# r6.net
KiCad netlist of a schematic drawn in EasyEDA
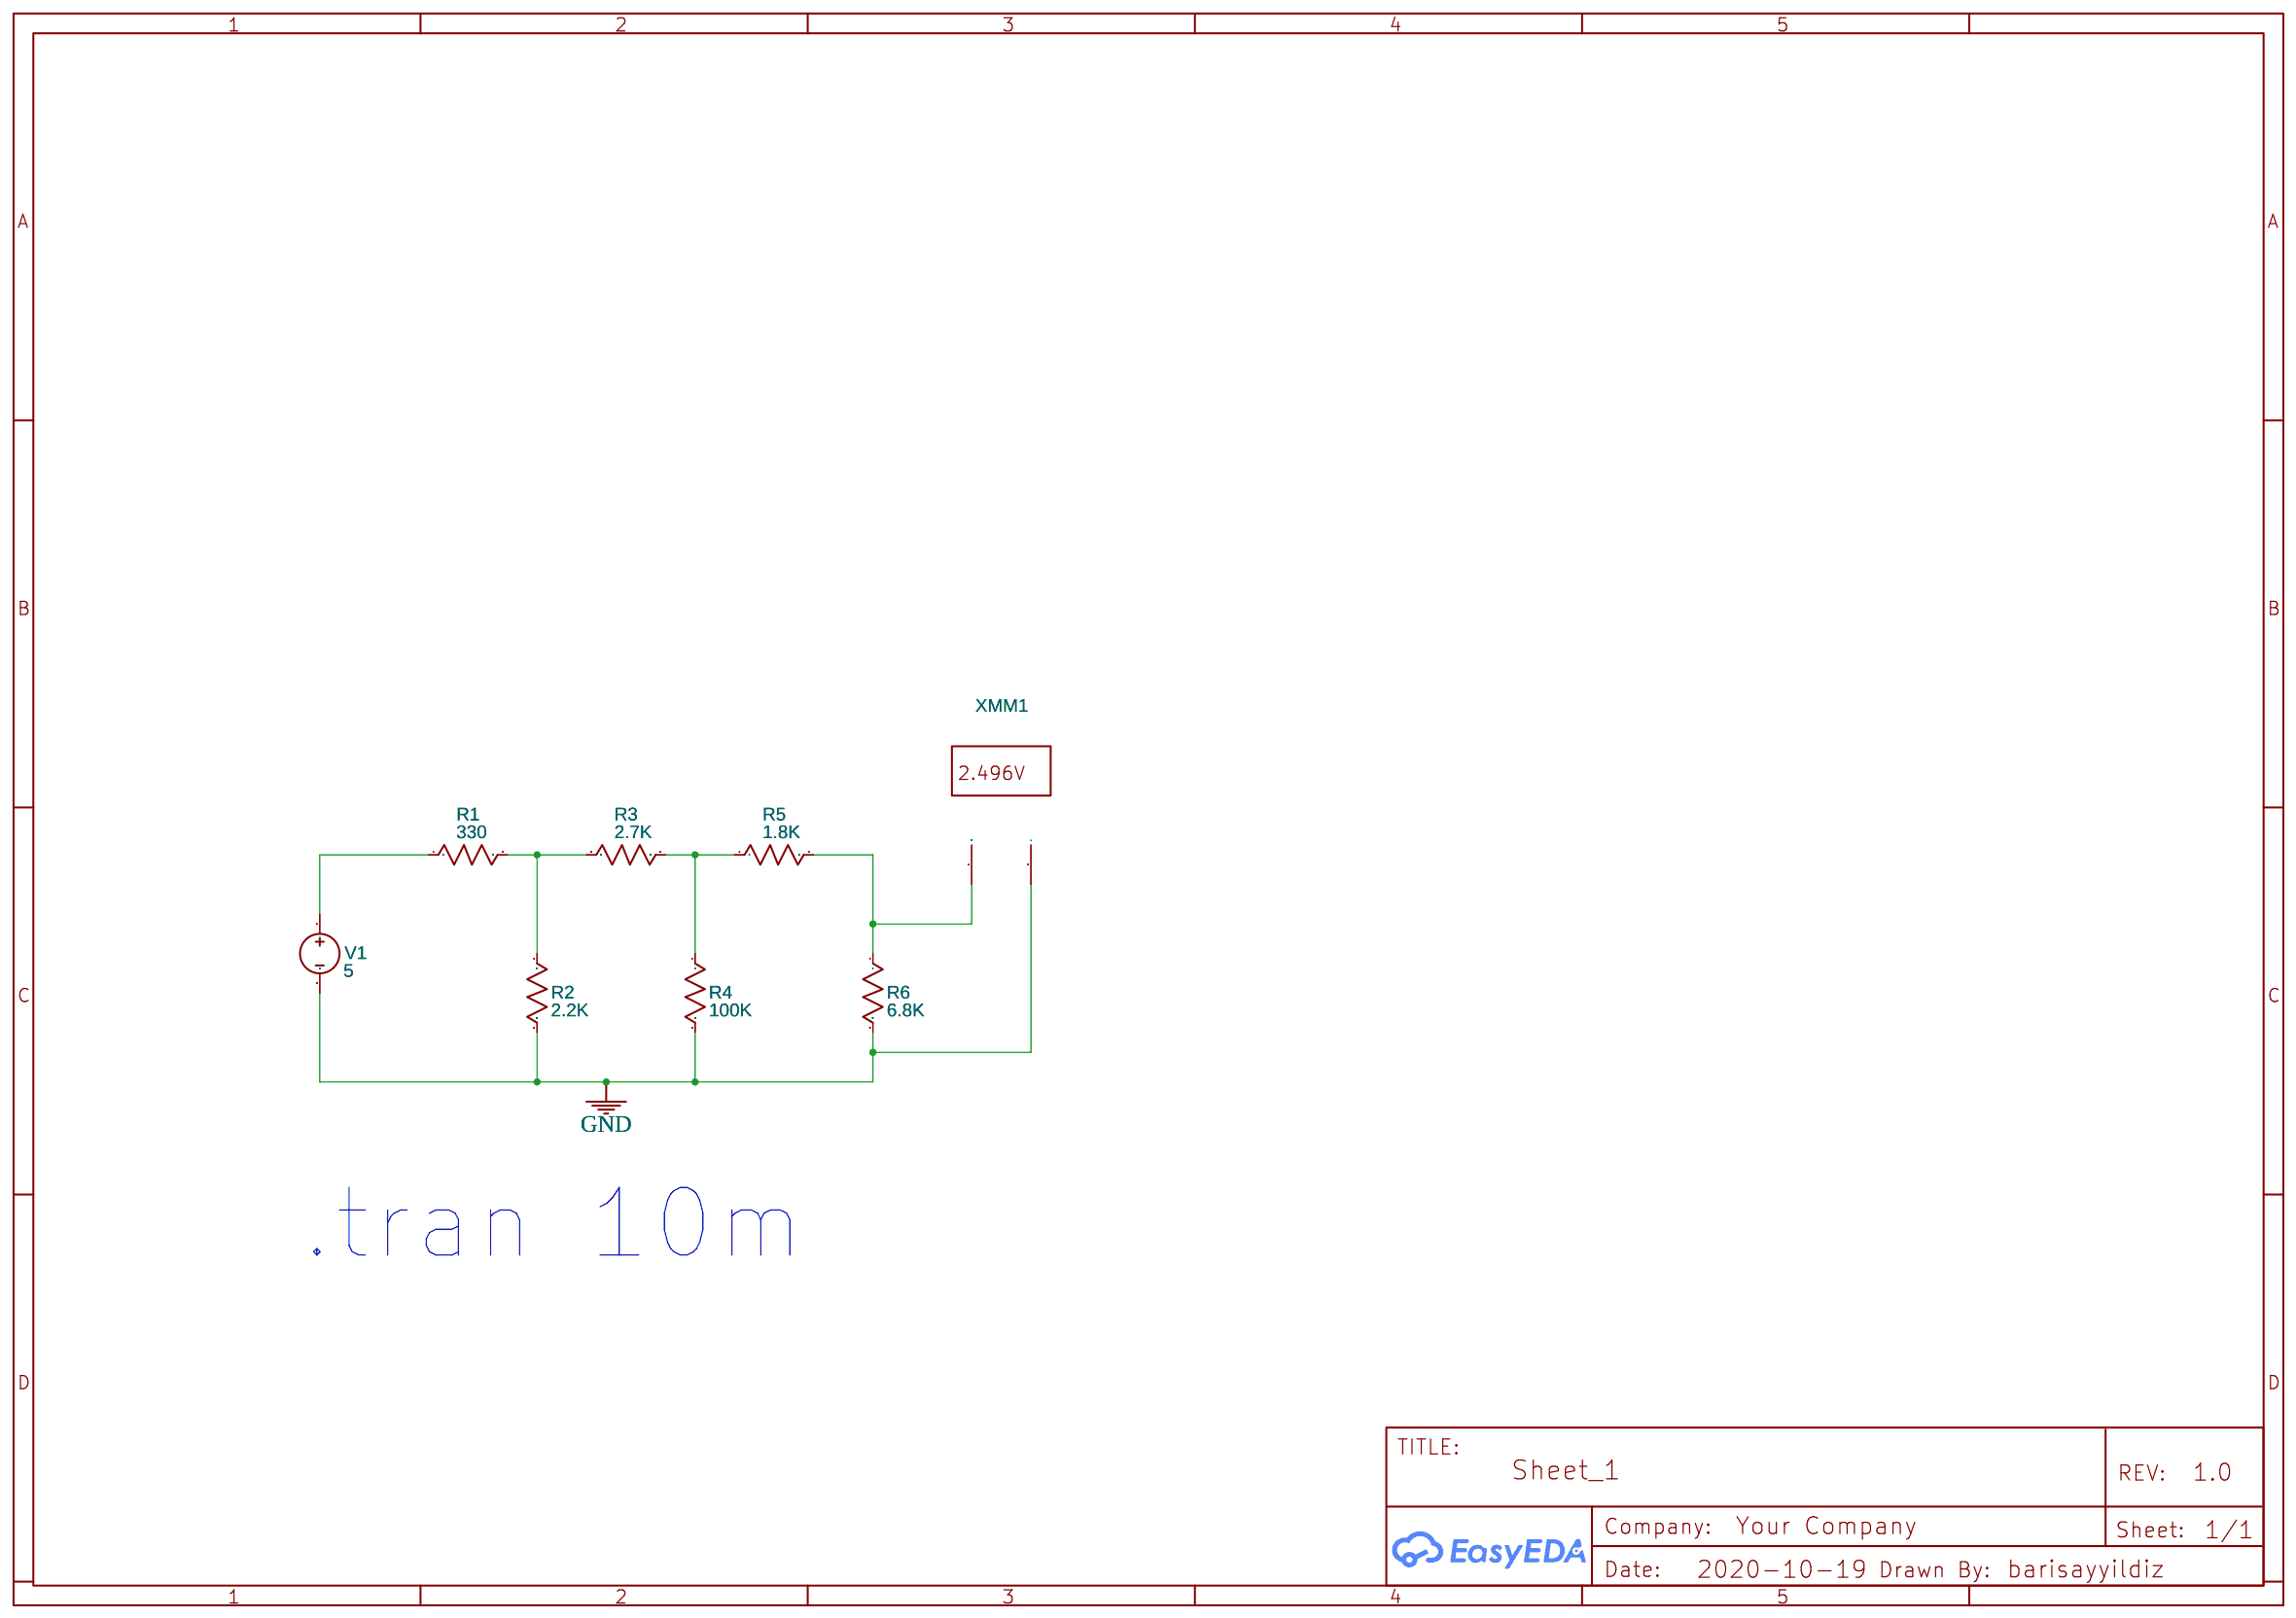
[diagram p0: schematic sheet]

(export (version "E")
  (design (tool "Eeschema 10.0.6"))
  (components
    (comp (ref "R1") (value "330") (libsource (lib "") (part "Resistor_US")))
    (comp (ref "R2") (value "2.2K") (libsource (lib "") (part "Resistor_US_1")))
    (comp (ref "R3") (value "2.7K") (libsource (lib "") (part "Resistor_US")))
    (comp (ref "R4") (value "100K") (libsource (lib "") (part "Resistor_US_1")))
    (comp (ref "R5") (value "1.8K") (libsource (lib "") (part "Resistor_US")))
    (comp (ref "R6") (value "6.8K") (libsource (lib "") (part "Resistor_US_1")))
    (comp (ref "V1") (value "5") (libsource (lib "") (part "VDC")))
    (comp (ref "XMM1") (value "Multimeter") (libsource (lib "") (part "MULTIMETER")))
  )
  (nets
    (net (code "1") (name "GND") (class "Default")
      (node (ref "R2") (pin "2") (pinfunction "2_2") (pintype "unspecified"))
      (node (ref "R4") (pin "2") (pinfunction "2_2") (pintype "unspecified"))
      (node (ref "R6") (pin "2") (pinfunction "2_2") (pintype "unspecified"))
      (node (ref "V1") (pin "2") (pinfunction "2_2") (pintype "unspecified"))
      (node (ref "XMM1") (pin "2") (pinfunction "I_2") (pintype "unspecified"))
    )
    (net (code "2") (name "Net-(R1-Pad1)") (class "Default")
      (node (ref "R1") (pin "1") (pinfunction "1_1") (pintype "unspecified"))
      (node (ref "V1") (pin "1") (pinfunction "1_1") (pintype "unspecified"))
    )
    (net (code "3") (name "Net-(R1-Pad2)") (class "Default")
      (node (ref "R1") (pin "2") (pinfunction "2_2") (pintype "unspecified"))
      (node (ref "R2") (pin "1") (pinfunction "1_1") (pintype "unspecified"))
      (node (ref "R3") (pin "1") (pinfunction "1_1") (pintype "unspecified"))
    )
    (net (code "4") (name "Net-(R3-Pad2)") (class "Default")
      (node (ref "R3") (pin "2") (pinfunction "2_2") (pintype "unspecified"))
      (node (ref "R4") (pin "1") (pinfunction "1_1") (pintype "unspecified"))
      (node (ref "R5") (pin "1") (pinfunction "1_1") (pintype "unspecified"))
    )
    (net (code "5") (name "Net-(XMM1-+)") (class "Default")
      (node (ref "R5") (pin "2") (pinfunction "2_2") (pintype "unspecified"))
      (node (ref "R6") (pin "1") (pinfunction "1_1") (pintype "unspecified"))
      (node (ref "XMM1") (pin "1") (pinfunction "+_1") (pintype "unspecified"))
    )
  )
)
